# 1_APO_Connectors.net
KiCad netlist of a schematic drawn in Altium Designer
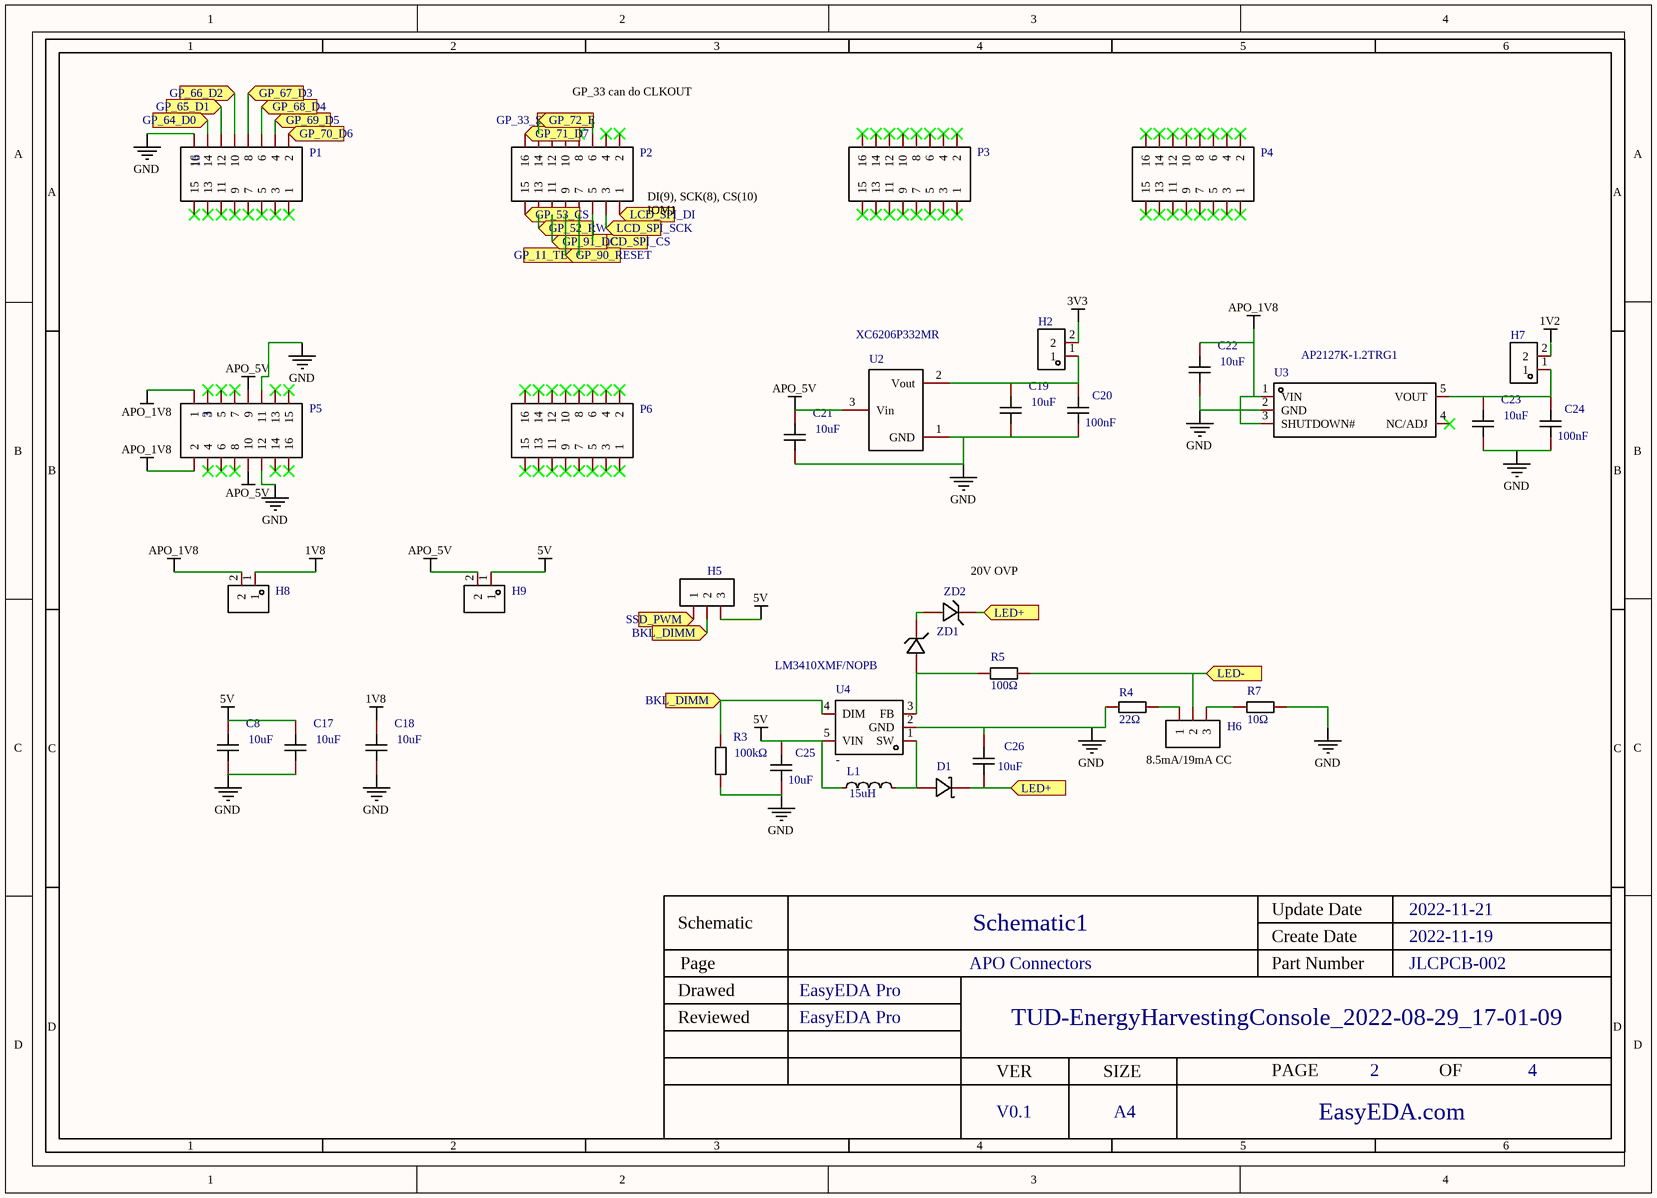
[diagram p0: 1_APO Connectors.schdoc]

(export (version "E")
  (design (tool "Eeschema 10.0.6"))
  (components
    (comp (ref "C8")
      (value "10uF")
      (fields
        (field (name "MANUFACTURER") "SAMSUNG(三星)")
        (field (name "MANUFACTURER PART") "CL10A106MA8NRNC")
        (field (name "TOLERANCE") "±20%")
      )
      (libsource (lib "altium-import") (part "root_1_CL10A106MA8NRNC_"))
    )
    (comp (ref "C17")
      (value "10uF")
      (fields
        (field (name "MANUFACTURER") "SAMSUNG(三星)")
        (field (name "MANUFACTURER PART") "CL10A106MA8NRNC")
        (field (name "TOLERANCE") "±20%")
      )
      (libsource (lib "altium-import") (part "root_1_CL10A106MA8NRNC_"))
    )
    (comp (ref "C18")
      (value "10uF")
      (fields
        (field (name "MANUFACTURER") "SAMSUNG(三星)")
        (field (name "MANUFACTURER PART") "CL10A106MA8NRNC")
        (field (name "TOLERANCE") "±20%")
      )
      (libsource (lib "altium-import") (part "root_1_CL10A106MA8NRNC_"))
    )
    (comp (ref "C19")
      (value "10uF")
      (fields
        (field (name "MANUFACTURER") "SAMSUNG(三星)")
        (field (name "MANUFACTURER PART") "CL10A106MA8NRNC")
        (field (name "TOLERANCE") "±20%")
      )
      (libsource (lib "altium-import") (part "root_1_CL10A106MA8NRNC_"))
    )
    (comp (ref "C20")
      (value "100nF")
      (fields
        (field (name "MANUFACTURER") "YAGEO(国巨)")
        (field (name "MANUFACTURER PART") "CC0603KRX7R9BB104")
        (field (name "TOLERANCE") "±10%")
      )
      (libsource (lib "altium-import") (part "root_1_CC0603KRX7R9BB104_"))
    )
    (comp (ref "C21")
      (value "10uF")
      (fields
        (field (name "MANUFACTURER") "SAMSUNG(三星)")
        (field (name "MANUFACTURER PART") "CL10A106MA8NRNC")
        (field (name "TOLERANCE") "±20%")
      )
      (libsource (lib "altium-import") (part "root_1_CL10A106MA8NRNC_"))
    )
    (comp (ref "C22")
      (value "10uF")
      (fields
        (field (name "MANUFACTURER") "SAMSUNG(三星)")
        (field (name "MANUFACTURER PART") "CL10A106MA8NRNC")
        (field (name "TOLERANCE") "±20%")
      )
      (libsource (lib "altium-import") (part "root_1_CL10A106MA8NRNC_"))
    )
    (comp (ref "C23")
      (value "10uF")
      (fields
        (field (name "MANUFACTURER") "SAMSUNG(三星)")
        (field (name "MANUFACTURER PART") "CL10A106MA8NRNC")
        (field (name "TOLERANCE") "±20%")
      )
      (libsource (lib "altium-import") (part "root_1_CL10A106MA8NRNC_"))
    )
    (comp (ref "C24")
      (value "100nF")
      (fields
        (field (name "MANUFACTURER") "YAGEO(国巨)")
        (field (name "MANUFACTURER PART") "CC0603KRX7R9BB104")
        (field (name "TOLERANCE") "±10%")
      )
      (libsource (lib "altium-import") (part "root_1_CC0603KRX7R9BB104_"))
    )
    (comp (ref "C25")
      (value "10uF")
      (fields
        (field (name "MANUFACTURER") "SAMSUNG(三星)")
        (field (name "MANUFACTURER PART") "CL10A106MA8NRNC")
        (field (name "TOLERANCE") "±20%")
      )
      (libsource (lib "altium-import") (part "root_1_CL10A106MA8NRNC_"))
    )
    (comp (ref "C26")
      (value "10uF")
      (fields
        (field (name "MANUFACTURER") "SAMSUNG(三星)")
        (field (name "MANUFACTURER PART") "CL10A106MA8NRNC")
        (field (name "TOLERANCE") "±20%")
      )
      (libsource (lib "altium-import") (part "root_1_CL10A106MA8NRNC_"))
    )
    (comp (ref "D1")
      (value "SS210_C14996")
      (description "Reverse Voltage (Vr):100V Average Rectified Current (Io):2A Forward Voltage (Vf@If):850mV@2A")
      (fields (field (name "MANUFACTURER") "MDD") (field (name "MANUFACTURER PART") "SS210"))
      (libsource (lib "altium-import") (part "root_2_SS210_C14996_"))
    )
    (comp (ref "H2")
      (value "PZ254V-11-02P")
      (fields (field (name "MANUFACTURER") "XFCN(兴飞)"))
      (libsource (lib "altium-import") (part "root_2_PZ254V-11-02P_"))
    )
    (comp (ref "H5")
      (value "2.54-1*3P针")
      (fields (field (name "MANUFACTURER") "BOOMELE(博穆精密)"))
      (libsource (lib "altium-import") (part "root_1_2.54-1*3P针_"))
    )
    (comp (ref "H6")
      (value "2.54-1*3P针")
      (fields (field (name "MANUFACTURER") "BOOMELE(博穆精密)"))
      (libsource (lib "altium-import") (part "root_3_mirrored_2.54-1*3P针_"))
    )
    (comp (ref "H7")
      (value "PZ254V-11-02P")
      (fields (field (name "MANUFACTURER") "XFCN(兴飞)"))
      (libsource (lib "altium-import") (part "root_2_PZ254V-11-02P_"))
    )
    (comp (ref "H8")
      (value "PZ254V-11-02P")
      (fields (field (name "MANUFACTURER") "XFCN(兴飞)"))
      (libsource (lib "altium-import") (part "root_3_PZ254V-11-02P_"))
    )
    (comp (ref "H9")
      (value "PZ254V-11-02P")
      (fields (field (name "MANUFACTURER") "XFCN(兴飞)"))
      (libsource (lib "altium-import") (part "root_3_PZ254V-11-02P_"))
    )
    (comp (ref "L1")
      (value "15uH")
      (description "Inductance:15uH Tolerance:±20% Tolerance:±20% Rated Current:1.2A DC Resistance (DCR):186mΩ")
      (fields (field (name "MANUFACTURER") "COILMX(迈翔科技)") (field (name "MANUFACTURER PART") "MSA43-150M"))
      (libsource (lib "altium-import") (part "root_0_MSA43-150M_"))
    )
    (comp (ref "P1")
      (value "2.54-2*8P针_C68234")
      (fields
        (field (name "MANUFACTURER") "BOOMELE(博穆精密)")
        (field (name "MANUFACTURER PART") "2.54-2*8P针")
        (field (name "NAME") "16")
      )
      (libsource (lib "altium-import") (part "root_1_mirrored_2.54-2*8P针_C68234_"))
    )
    (comp (ref "P2")
      (value "2.54-2*8P针_C68234")
      (fields (field (name "MANUFACTURER") "BOOMELE(博穆精密)") (field (name "MANUFACTURER PART") "2.54-2*8P针"))
      (libsource (lib "altium-import") (part "root_1_mirrored_2.54-2*8P针_C68234_"))
    )
    (comp (ref "P3")
      (value "2.54-2*8P针_C68234")
      (fields (field (name "MANUFACTURER") "BOOMELE(博穆精密)") (field (name "MANUFACTURER PART") "2.54-2*8P针"))
      (libsource (lib "altium-import") (part "root_1_mirrored_2.54-2*8P针_C68234_"))
    )
    (comp (ref "P4")
      (value "2.54-2*8P针_C68234")
      (fields (field (name "MANUFACTURER") "BOOMELE(博穆精密)") (field (name "MANUFACTURER PART") "2.54-2*8P针"))
      (libsource (lib "altium-import") (part "root_1_mirrored_2.54-2*8P针_C68234_"))
    )
    (comp (ref "P5")
      (value "2.54-2*8P针_C68234")
      (fields
        (field (name "MANUFACTURER") "BOOMELE(博穆精密)")
        (field (name "MANUFACTURER PART") "2.54-2*8P针")
        (field (name "NAME") "3")
      )
      (libsource (lib "altium-import") (part "root_3_mirrored_2.54-2*8P针_C68234_"))
    )
    (comp (ref "P6")
      (value "2.54-2*8P针_C68234")
      (fields (field (name "MANUFACTURER") "BOOMELE(博穆精密)") (field (name "MANUFACTURER PART") "2.54-2*8P针"))
      (libsource (lib "altium-import") (part "root_1_mirrored_2.54-2*8P针_C68234_"))
    )
    (comp (ref "R3")
      (value "100kΩ")
      (fields
        (field (name "MANUFACTURER") "UNI-ROYAL(厚声)")
        (field (name "MANUFACTURER PART") "0603WAF1003T5E")
        (field (name "TOLERANCE") "±1%")
      )
      (libsource (lib "altium-import") (part "root_1_0603WAF1003T5E_"))
    )
    (comp (ref "R4")
      (value "22Ω")
      (fields
        (field (name "MANUFACTURER") "UNI-ROYAL(厚声)")
        (field (name "MANUFACTURER PART") "0603WAF220JT5E")
        (field (name "TOLERANCE") "±1%")
      )
      (libsource (lib "altium-import") (part "root_2_0603WAF220JT5E_"))
    )
    (comp (ref "R5")
      (value "100Ω")
      (fields
        (field (name "MANUFACTURER") "UNI-ROYAL(厚声)")
        (field (name "MANUFACTURER PART") "0603WAF1000T5E")
        (field (name "TOLERANCE") "±1%")
      )
      (libsource (lib "altium-import") (part "root_0_0603WAF1000T5E_"))
    )
    (comp (ref "R7")
      (value "10Ω")
      (fields (field (name "MANUFACTURER") "FH(风华)") (field (name "MANUFACTURER PART") "RS-03K10R0FT"))
      (libsource (lib "altium-import") (part "root_0_RS-03K10R0FT_"))
    )
    (comp (ref "U2")
      (value "XC6206P332MR_C5446")
      (fields (field (name "MANUFACTURER") "TOREX(特瑞仕)") (field (name "MANUFACTURER PART") "XC6206P332MR"))
      (libsource (lib "altium-import") (part "root_0_XC6206P332MR_C5446_"))
    )
    (comp (ref "U3")
      (value "AP2127K-1.2TRG1")
      (fields (field (name "MANUFACTURER") "DIODES(美台)") (field (name "MANUFACTURER PART") "AP2127K-1.2TRG1"))
      (libsource (lib "altium-import") (part "root_0_AP2127K-1.2TRG1_"))
    )
    (comp (ref "U4")
      (value "-")
      (fields
        (field (name "LCSC PART NAME") "LM3410XMF/NOPB")
        (field (name "MANUFACTURER") "TI(德州仪器)")
        (field (name "MANUFACTURER PART") "LM3410XMF/NOPB")
      )
      (libsource (lib "altium-import") (part "root_2_LM3410XMF/NOPB_"))
    )
    (comp (ref "ZD1")
      (value "MMSZ5240B_C21564")
      (fields (field (name "MANUFACTURER") "CJ（江苏长电/长晶）") (field (name "MANUFACTURER PART") "MMSZ5240B"))
      (libsource (lib "altium-import") (part "root_3_MMSZ5240B_C21564_"))
    )
    (comp (ref "ZD2")
      (value "MMSZ5240B_C21564")
      (fields (field (name "MANUFACTURER") "CJ（江苏长电/长晶）") (field (name "MANUFACTURER PART") "MMSZ5240B"))
      (libsource (lib "altium-import") (part "root_2_MMSZ5240B_C21564_"))
    )
  )
  (nets
    (net (code "1") (name "/BKL_DIMM") (class "Default")
      (node (ref "H5") (pin "2") (pinfunction "2_2") (pintype "passive"))
      (node (ref "R3") (pin "2") (pinfunction "2_2") (pintype "passive"))
      (node (ref "U4") (pin "4") (pinfunction "DIM_4") (pintype "passive"))
    )
    (net (code "2") (name "/GP_11_TE") (class "Default")
      (node (ref "P2") (pin "7") (pinfunction "7_7") (pintype "passive"))
    )
    (net (code "3") (name "/GP_33_SSDCLK") (class "Default")
      (node (ref "P2") (pin "6") (pinfunction "6_6") (pintype "passive"))
    )
    (net (code "4") (name "/GP_52_RW") (class "Default")
      (node (ref "P2") (pin "13") (pinfunction "13_13") (pintype "passive"))
    )
    (net (code "5") (name "/GP_53_CS") (class "Default")
      (node (ref "P2") (pin "15") (pinfunction "15_15") (pintype "passive"))
    )
    (net (code "6") (name "/GP_64_D0") (class "Default")
      (node (ref "P1") (pin "14") (pinfunction "14_14") (pintype "passive"))
    )
    (net (code "7") (name "/GP_65_D1") (class "Default")
      (node (ref "P1") (pin "12") (pinfunction "12_12") (pintype "passive"))
    )
    (net (code "8") (name "/GP_66_D2") (class "Default")
      (node (ref "P1") (pin "10") (pinfunction "10_10") (pintype "passive"))
    )
    (net (code "9") (name "/GP_67_D3") (class "Default")
      (node (ref "P1") (pin "8") (pinfunction "8_8") (pintype "passive"))
    )
    (net (code "10") (name "/GP_68_D4") (class "Default")
      (node (ref "P1") (pin "6") (pinfunction "6_6") (pintype "passive"))
    )
    (net (code "11") (name "/GP_69_D5") (class "Default")
      (node (ref "P1") (pin "4") (pinfunction "4_4") (pintype "passive"))
    )
    (net (code "12") (name "/GP_70_D6") (class "Default")
      (node (ref "P1") (pin "2") (pinfunction "2_2") (pintype "passive"))
    )
    (net (code "13") (name "/GP_71_D7") (class "Default")
      (node (ref "P2") (pin "16") (pinfunction "16_16") (pintype "passive"))
    )
    (net (code "14") (name "/GP_72_E") (class "Default")
      (node (ref "P2") (pin "14") (pinfunction "14_14") (pintype "passive"))
    )
    (net (code "15") (name "/GP_90_RESET") (class "Default")
      (node (ref "P2") (pin "9") (pinfunction "9_9") (pintype "passive"))
    )
    (net (code "16") (name "/GP_91_DC") (class "Default")
      (node (ref "P2") (pin "11") (pinfunction "11_11") (pintype "passive"))
    )
    (net (code "17") (name "/LCD_SPI_CS") (class "Default")
      (node (ref "P2") (pin "5") (pinfunction "5_5") (pintype "passive"))
    )
    (net (code "18") (name "/LCD_SPI_DI") (class "Default")
      (node (ref "P2") (pin "1") (pinfunction "1_1") (pintype "passive"))
    )
    (net (code "19") (name "/LCD_SPI_SCK") (class "Default")
      (node (ref "P2") (pin "3") (pinfunction "3_3") (pintype "passive"))
    )
    (net (code "20") (name "/LED+") (class "Default")
      (node (ref "C26") (pin "1") (pinfunction "1_1") (pintype "passive"))
      (node (ref "D1") (pin "1") (pinfunction "K_1") (pintype "passive"))
      (node (ref "ZD2") (pin "1") (pinfunction "K_1") (pintype "passive"))
    )
    (net (code "21") (name "/LED-") (class "Default")
      (node (ref "H6") (pin "2") (pinfunction "2_2") (pintype "passive"))
      (node (ref "R5") (pin "2") (pinfunction "2_2") (pintype "passive"))
    )
    (net (code "22") (name "/SSD_PWM") (class "Default")
      (node (ref "H5") (pin "1") (pinfunction "1_1") (pintype "passive"))
    )
    (net (code "23") (name "1V2") (class "Default")
      (node (ref "H7") (pin "2") (pinfunction "2_2") (pintype "passive"))
    )
    (net (code "24") (name "1V8") (class "Default")
      (node (ref "C18") (pin "2") (pinfunction "2_2") (pintype "passive"))
      (node (ref "H8") (pin "1") (pinfunction "1_1") (pintype "passive"))
    )
    (net (code "25") (name "3V3") (class "Default")
      (node (ref "H2") (pin "2") (pinfunction "2_2") (pintype "passive"))
    )
    (net (code "26") (name "5V") (class "Default")
      (node (ref "C17") (pin "2") (pinfunction "2_2") (pintype "passive"))
      (node (ref "C25") (pin "2") (pinfunction "2_2") (pintype "passive"))
      (node (ref "C8") (pin "2") (pinfunction "2_2") (pintype "passive"))
      (node (ref "H5") (pin "3") (pinfunction "3_3") (pintype "passive"))
      (node (ref "H9") (pin "1") (pinfunction "1_1") (pintype "passive"))
      (node (ref "L1") (pin "1") (pinfunction "1_1") (pintype "passive"))
      (node (ref "U4") (pin "5") (pinfunction "VIN_5") (pintype "passive"))
    )
    (net (code "27") (name "APO_1V8") (class "Default")
      (node (ref "C22") (pin "2") (pinfunction "2_2") (pintype "passive"))
      (node (ref "H8") (pin "2") (pinfunction "2_2") (pintype "passive"))
      (node (ref "P5") (pin "1") (pinfunction "1_1") (pintype "passive"))
      (node (ref "P5") (pin "2") (pinfunction "2_2") (pintype "passive"))
      (node (ref "U3") (pin "1") (pinfunction "VIN_1") (pintype "passive"))
      (node (ref "U3") (pin "3") (pinfunction "SHUTDOWN#_3") (pintype "passive"))
    )
    (net (code "28") (name "APO_5V") (class "Default")
      (node (ref "C21") (pin "2") (pinfunction "2_2") (pintype "passive"))
      (node (ref "H9") (pin "2") (pinfunction "2_2") (pintype "passive"))
      (node (ref "P5") (pin "10") (pinfunction "10_10") (pintype "passive"))
      (node (ref "P5") (pin "9") (pinfunction "9_9") (pintype "passive"))
      (node (ref "U2") (pin "3") (pinfunction "Vin_3") (pintype "passive"))
    )
    (net (code "29") (name "GND") (class "Default")
      (node (ref "C17") (pin "1") (pinfunction "1_1") (pintype "passive"))
      (node (ref "C18") (pin "1") (pinfunction "1_1") (pintype "passive"))
      (node (ref "C19") (pin "1") (pinfunction "1_1") (pintype "passive"))
      (node (ref "C20") (pin "1") (pinfunction "1_1") (pintype "passive"))
      (node (ref "C21") (pin "1") (pinfunction "1_1") (pintype "passive"))
      (node (ref "C22") (pin "1") (pinfunction "1_1") (pintype "passive"))
      (node (ref "C23") (pin "1") (pinfunction "1_1") (pintype "passive"))
      (node (ref "C24") (pin "1") (pinfunction "1_1") (pintype "passive"))
      (node (ref "C25") (pin "1") (pinfunction "1_1") (pintype "passive"))
      (node (ref "C26") (pin "2") (pinfunction "2_2") (pintype "passive"))
      (node (ref "C8") (pin "1") (pinfunction "1_1") (pintype "passive"))
      (node (ref "P1") (pin "16") (pinfunction "16_16") (pintype "passive"))
      (node (ref "P5") (pin "11") (pinfunction "11_11") (pintype "passive"))
      (node (ref "P5") (pin "12") (pinfunction "12_12") (pintype "passive"))
      (node (ref "R3") (pin "1") (pinfunction "1_1") (pintype "passive"))
      (node (ref "R4") (pin "2") (pinfunction "2_2") (pintype "passive"))
      (node (ref "R7") (pin "2") (pinfunction "2_2") (pintype "passive"))
      (node (ref "U2") (pin "1") (pinfunction "GND_1") (pintype "passive"))
      (node (ref "U3") (pin "2") (pinfunction "GND_2") (pintype "passive"))
      (node (ref "U4") (pin "2") (pinfunction "GND_2") (pintype "passive"))
    )
    (net (code "30") (name "Net-(D1-A)") (class "Default")
      (node (ref "D1") (pin "2") (pinfunction "A_2") (pintype "passive"))
      (node (ref "L1") (pin "2") (pinfunction "2_2") (pintype "passive"))
      (node (ref "U4") (pin "1") (pinfunction "SW_1") (pintype "passive"))
    )
    (net (code "31") (name "Net-(H6-Pad1)") (class "Default")
      (node (ref "H6") (pin "1") (pinfunction "1_1") (pintype "passive"))
      (node (ref "R4") (pin "1") (pinfunction "1_1") (pintype "passive"))
    )
    (net (code "32") (name "Net-(H6-Pad3)") (class "Default")
      (node (ref "H6") (pin "3") (pinfunction "3_3") (pintype "passive"))
      (node (ref "R7") (pin "1") (pinfunction "1_1") (pintype "passive"))
    )
    (net (code "33") (name "Net-(U2-Vout)") (class "Default")
      (node (ref "C19") (pin "2") (pinfunction "2_2") (pintype "passive"))
      (node (ref "C20") (pin "2") (pinfunction "2_2") (pintype "passive"))
      (node (ref "H2") (pin "1") (pinfunction "1_1") (pintype "passive"))
      (node (ref "U2") (pin "2") (pinfunction "Vout_2") (pintype "passive"))
    )
    (net (code "34") (name "Net-(U3-VOUT)") (class "Default")
      (node (ref "C23") (pin "2") (pinfunction "2_2") (pintype "passive"))
      (node (ref "C24") (pin "2") (pinfunction "2_2") (pintype "passive"))
      (node (ref "H7") (pin "1") (pinfunction "1_1") (pintype "passive"))
      (node (ref "U3") (pin "5") (pinfunction "VOUT_5") (pintype "passive"))
    )
    (net (code "35") (name "Net-(U4-FB)") (class "Default")
      (node (ref "R5") (pin "1") (pinfunction "1_1") (pintype "passive"))
      (node (ref "U4") (pin "3") (pinfunction "FB_3") (pintype "passive"))
      (node (ref "ZD1") (pin "2") (pinfunction "A_2") (pintype "passive"))
    )
    (net (code "36") (name "Net-(ZD1-K)") (class "Default")
      (node (ref "ZD1") (pin "1") (pinfunction "K_1") (pintype "passive"))
      (node (ref "ZD2") (pin "2") (pinfunction "A_2") (pintype "passive"))
    )
    (net (code "37") (name "unconnected-(P1-Pad1)") (class "Default")
      (node (ref "P1") (pin "1") (pinfunction "1_1") (pintype "passive+no_connect"))
    )
    (net (code "38") (name "unconnected-(P1-Pad3)") (class "Default")
      (node (ref "P1") (pin "3") (pinfunction "3_3") (pintype "passive+no_connect"))
    )
    (net (code "39") (name "unconnected-(P1-Pad5)") (class "Default")
      (node (ref "P1") (pin "5") (pinfunction "5_5") (pintype "passive+no_connect"))
    )
    (net (code "40") (name "unconnected-(P1-Pad7)") (class "Default")
      (node (ref "P1") (pin "7") (pinfunction "7_7") (pintype "passive+no_connect"))
    )
    (net (code "41") (name "unconnected-(P1-Pad9)") (class "Default")
      (node (ref "P1") (pin "9") (pinfunction "9_9") (pintype "passive+no_connect"))
    )
    (net (code "42") (name "unconnected-(P1-Pad11)") (class "Default")
      (node (ref "P1") (pin "11") (pinfunction "11_11") (pintype "passive+no_connect"))
    )
    (net (code "43") (name "unconnected-(P1-Pad13)") (class "Default")
      (node (ref "P1") (pin "13") (pinfunction "13_13") (pintype "passive+no_connect"))
    )
    (net (code "44") (name "unconnected-(P1-Pad15)") (class "Default")
      (node (ref "P1") (pin "15") (pinfunction "15_15") (pintype "passive+no_connect"))
    )
    (net (code "45") (name "unconnected-(P2-Pad2)") (class "Default")
      (node (ref "P2") (pin "2") (pinfunction "2_2") (pintype "passive+no_connect"))
    )
    (net (code "46") (name "unconnected-(P2-Pad4)") (class "Default")
      (node (ref "P2") (pin "4") (pinfunction "4_4") (pintype "passive+no_connect"))
    )
    (net (code "47") (name "unconnected-(P2-Pad8)") (class "Default")
      (node (ref "P2") (pin "8") (pinfunction "8_8") (pintype "passive+no_connect"))
    )
    (net (code "48") (name "unconnected-(P2-Pad10)") (class "Default")
      (node (ref "P2") (pin "10") (pinfunction "10_10") (pintype "passive+no_connect"))
    )
    (net (code "49") (name "unconnected-(P2-Pad12)") (class "Default")
      (node (ref "P2") (pin "12") (pinfunction "12_12") (pintype "passive+no_connect"))
    )
    (net (code "50") (name "unconnected-(P3-Pad1)") (class "Default")
      (node (ref "P3") (pin "1") (pinfunction "1_1") (pintype "passive+no_connect"))
    )
    (net (code "51") (name "unconnected-(P3-Pad2)") (class "Default")
      (node (ref "P3") (pin "2") (pinfunction "2_2") (pintype "passive+no_connect"))
    )
    (net (code "52") (name "unconnected-(P3-Pad3)") (class "Default")
      (node (ref "P3") (pin "3") (pinfunction "3_3") (pintype "passive+no_connect"))
    )
    (net (code "53") (name "unconnected-(P3-Pad4)") (class "Default")
      (node (ref "P3") (pin "4") (pinfunction "4_4") (pintype "passive+no_connect"))
    )
    (net (code "54") (name "unconnected-(P3-Pad5)") (class "Default")
      (node (ref "P3") (pin "5") (pinfunction "5_5") (pintype "passive+no_connect"))
    )
    (net (code "55") (name "unconnected-(P3-Pad6)") (class "Default")
      (node (ref "P3") (pin "6") (pinfunction "6_6") (pintype "passive+no_connect"))
    )
    (net (code "56") (name "unconnected-(P3-Pad7)") (class "Default")
      (node (ref "P3") (pin "7") (pinfunction "7_7") (pintype "passive+no_connect"))
    )
    (net (code "57") (name "unconnected-(P3-Pad8)") (class "Default")
      (node (ref "P3") (pin "8") (pinfunction "8_8") (pintype "passive+no_connect"))
    )
    (net (code "58") (name "unconnected-(P3-Pad9)") (class "Default")
      (node (ref "P3") (pin "9") (pinfunction "9_9") (pintype "passive+no_connect"))
    )
    (net (code "59") (name "unconnected-(P3-Pad10)") (class "Default")
      (node (ref "P3") (pin "10") (pinfunction "10_10") (pintype "passive+no_connect"))
    )
    (net (code "60") (name "unconnected-(P3-Pad11)") (class "Default")
      (node (ref "P3") (pin "11") (pinfunction "11_11") (pintype "passive+no_connect"))
    )
    (net (code "61") (name "unconnected-(P3-Pad12)") (class "Default")
      (node (ref "P3") (pin "12") (pinfunction "12_12") (pintype "passive+no_connect"))
    )
    (net (code "62") (name "unconnected-(P3-Pad13)") (class "Default")
      (node (ref "P3") (pin "13") (pinfunction "13_13") (pintype "passive+no_connect"))
    )
    (net (code "63") (name "unconnected-(P3-Pad14)") (class "Default")
      (node (ref "P3") (pin "14") (pinfunction "14_14") (pintype "passive+no_connect"))
    )
    (net (code "64") (name "unconnected-(P3-Pad15)") (class "Default")
      (node (ref "P3") (pin "15") (pinfunction "15_15") (pintype "passive+no_connect"))
    )
    (net (code "65") (name "unconnected-(P3-Pad16)") (class "Default")
      (node (ref "P3") (pin "16") (pinfunction "16_16") (pintype "passive+no_connect"))
    )
    (net (code "66") (name "unconnected-(P4-Pad1)") (class "Default")
      (node (ref "P4") (pin "1") (pinfunction "1_1") (pintype "passive+no_connect"))
    )
    (net (code "67") (name "unconnected-(P4-Pad2)") (class "Default")
      (node (ref "P4") (pin "2") (pinfunction "2_2") (pintype "passive+no_connect"))
    )
    (net (code "68") (name "unconnected-(P4-Pad3)") (class "Default")
      (node (ref "P4") (pin "3") (pinfunction "3_3") (pintype "passive+no_connect"))
    )
    (net (code "69") (name "unconnected-(P4-Pad4)") (class "Default")
      (node (ref "P4") (pin "4") (pinfunction "4_4") (pintype "passive+no_connect"))
    )
    (net (code "70") (name "unconnected-(P4-Pad5)") (class "Default")
      (node (ref "P4") (pin "5") (pinfunction "5_5") (pintype "passive+no_connect"))
    )
    (net (code "71") (name "unconnected-(P4-Pad6)") (class "Default")
      (node (ref "P4") (pin "6") (pinfunction "6_6") (pintype "passive+no_connect"))
    )
    (net (code "72") (name "unconnected-(P4-Pad7)") (class "Default")
      (node (ref "P4") (pin "7") (pinfunction "7_7") (pintype "passive+no_connect"))
    )
    (net (code "73") (name "unconnected-(P4-Pad8)") (class "Default")
      (node (ref "P4") (pin "8") (pinfunction "8_8") (pintype "passive+no_connect"))
    )
    (net (code "74") (name "unconnected-(P4-Pad9)") (class "Default")
      (node (ref "P4") (pin "9") (pinfunction "9_9") (pintype "passive+no_connect"))
    )
    (net (code "75") (name "unconnected-(P4-Pad10)") (class "Default")
      (node (ref "P4") (pin "10") (pinfunction "10_10") (pintype "passive+no_connect"))
    )
    (net (code "76") (name "unconnected-(P4-Pad11)") (class "Default")
      (node (ref "P4") (pin "11") (pinfunction "11_11") (pintype "passive+no_connect"))
    )
    (net (code "77") (name "unconnected-(P4-Pad12)") (class "Default")
      (node (ref "P4") (pin "12") (pinfunction "12_12") (pintype "passive+no_connect"))
    )
    (net (code "78") (name "unconnected-(P4-Pad13)") (class "Default")
      (node (ref "P4") (pin "13") (pinfunction "13_13") (pintype "passive+no_connect"))
    )
    (net (code "79") (name "unconnected-(P4-Pad14)") (class "Default")
      (node (ref "P4") (pin "14") (pinfunction "14_14") (pintype "passive+no_connect"))
    )
    (net (code "80") (name "unconnected-(P4-Pad15)") (class "Default")
      (node (ref "P4") (pin "15") (pinfunction "15_15") (pintype "passive+no_connect"))
    )
    (net (code "81") (name "unconnected-(P4-Pad16)") (class "Default")
      (node (ref "P4") (pin "16") (pinfunction "16_16") (pintype "passive+no_connect"))
    )
    (net (code "82") (name "unconnected-(P5-Pad3)") (class "Default")
      (node (ref "P5") (pin "3") (pinfunction "3_3") (pintype "passive+no_connect"))
    )
    (net (code "83") (name "unconnected-(P5-Pad4)") (class "Default")
      (node (ref "P5") (pin "4") (pinfunction "4_4") (pintype "passive+no_connect"))
    )
    (net (code "84") (name "unconnected-(P5-Pad5)") (class "Default")
      (node (ref "P5") (pin "5") (pinfunction "5_5") (pintype "passive+no_connect"))
    )
    (net (code "85") (name "unconnected-(P5-Pad6)") (class "Default")
      (node (ref "P5") (pin "6") (pinfunction "6_6") (pintype "passive+no_connect"))
    )
    (net (code "86") (name "unconnected-(P5-Pad7)") (class "Default")
      (node (ref "P5") (pin "7") (pinfunction "7_7") (pintype "passive+no_connect"))
    )
    (net (code "87") (name "unconnected-(P5-Pad8)") (class "Default")
      (node (ref "P5") (pin "8") (pinfunction "8_8") (pintype "passive+no_connect"))
    )
    (net (code "88") (name "unconnected-(P5-Pad13)") (class "Default")
      (node (ref "P5") (pin "13") (pinfunction "13_13") (pintype "passive+no_connect"))
    )
    (net (code "89") (name "unconnected-(P5-Pad14)") (class "Default")
      (node (ref "P5") (pin "14") (pinfunction "14_14") (pintype "passive+no_connect"))
    )
    (net (code "90") (name "unconnected-(P5-Pad15)") (class "Default")
      (node (ref "P5") (pin "15") (pinfunction "15_15") (pintype "passive+no_connect"))
    )
    (net (code "91") (name "unconnected-(P5-Pad16)") (class "Default")
      (node (ref "P5") (pin "16") (pinfunction "16_16") (pintype "passive+no_connect"))
    )
    (net (code "92") (name "unconnected-(P6-Pad1)") (class "Default")
      (node (ref "P6") (pin "1") (pinfunction "1_1") (pintype "passive+no_connect"))
    )
    (net (code "93") (name "unconnected-(P6-Pad2)") (class "Default")
      (node (ref "P6") (pin "2") (pinfunction "2_2") (pintype "passive+no_connect"))
    )
    (net (code "94") (name "unconnected-(P6-Pad3)") (class "Default")
      (node (ref "P6") (pin "3") (pinfunction "3_3") (pintype "passive+no_connect"))
    )
    (net (code "95") (name "unconnected-(P6-Pad4)") (class "Default")
      (node (ref "P6") (pin "4") (pinfunction "4_4") (pintype "passive+no_connect"))
    )
    (net (code "96") (name "unconnected-(P6-Pad5)") (class "Default")
      (node (ref "P6") (pin "5") (pinfunction "5_5") (pintype "passive+no_connect"))
    )
    (net (code "97") (name "unconnected-(P6-Pad6)") (class "Default")
      (node (ref "P6") (pin "6") (pinfunction "6_6") (pintype "passive+no_connect"))
    )
    (net (code "98") (name "unconnected-(P6-Pad7)") (class "Default")
      (node (ref "P6") (pin "7") (pinfunction "7_7") (pintype "passive+no_connect"))
    )
    (net (code "99") (name "unconnected-(P6-Pad8)") (class "Default")
      (node (ref "P6") (pin "8") (pinfunction "8_8") (pintype "passive+no_connect"))
    )
    (net (code "100") (name "unconnected-(P6-Pad9)") (class "Default")
      (node (ref "P6") (pin "9") (pinfunction "9_9") (pintype "passive+no_connect"))
    )
    (net (code "101") (name "unconnected-(P6-Pad10)") (class "Default")
      (node (ref "P6") (pin "10") (pinfunction "10_10") (pintype "passive+no_connect"))
    )
    (net (code "102") (name "unconnected-(P6-Pad11)") (class "Default")
      (node (ref "P6") (pin "11") (pinfunction "11_11") (pintype "passive+no_connect"))
    )
    (net (code "103") (name "unconnected-(P6-Pad12)") (class "Default")
      (node (ref "P6") (pin "12") (pinfunction "12_12") (pintype "passive+no_connect"))
    )
    (net (code "104") (name "unconnected-(P6-Pad13)") (class "Default")
      (node (ref "P6") (pin "13") (pinfunction "13_13") (pintype "passive+no_connect"))
    )
    (net (code "105") (name "unconnected-(P6-Pad14)") (class "Default")
      (node (ref "P6") (pin "14") (pinfunction "14_14") (pintype "passive+no_connect"))
    )
    (net (code "106") (name "unconnected-(P6-Pad15)") (class "Default")
      (node (ref "P6") (pin "15") (pinfunction "15_15") (pintype "passive+no_connect"))
    )
    (net (code "107") (name "unconnected-(P6-Pad16)") (class "Default")
      (node (ref "P6") (pin "16") (pinfunction "16_16") (pintype "passive+no_connect"))
    )
    (net (code "108") (name "unconnected-(U3-NC{slash}ADJ-Pad4)") (class "Default")
      (node (ref "U3") (pin "4") (pinfunction "NC/ADJ_4") (pintype "passive+no_connect"))
    )
  )
)
